# sch.net
KiCad netlist of a schematic drawn in Altium Designer
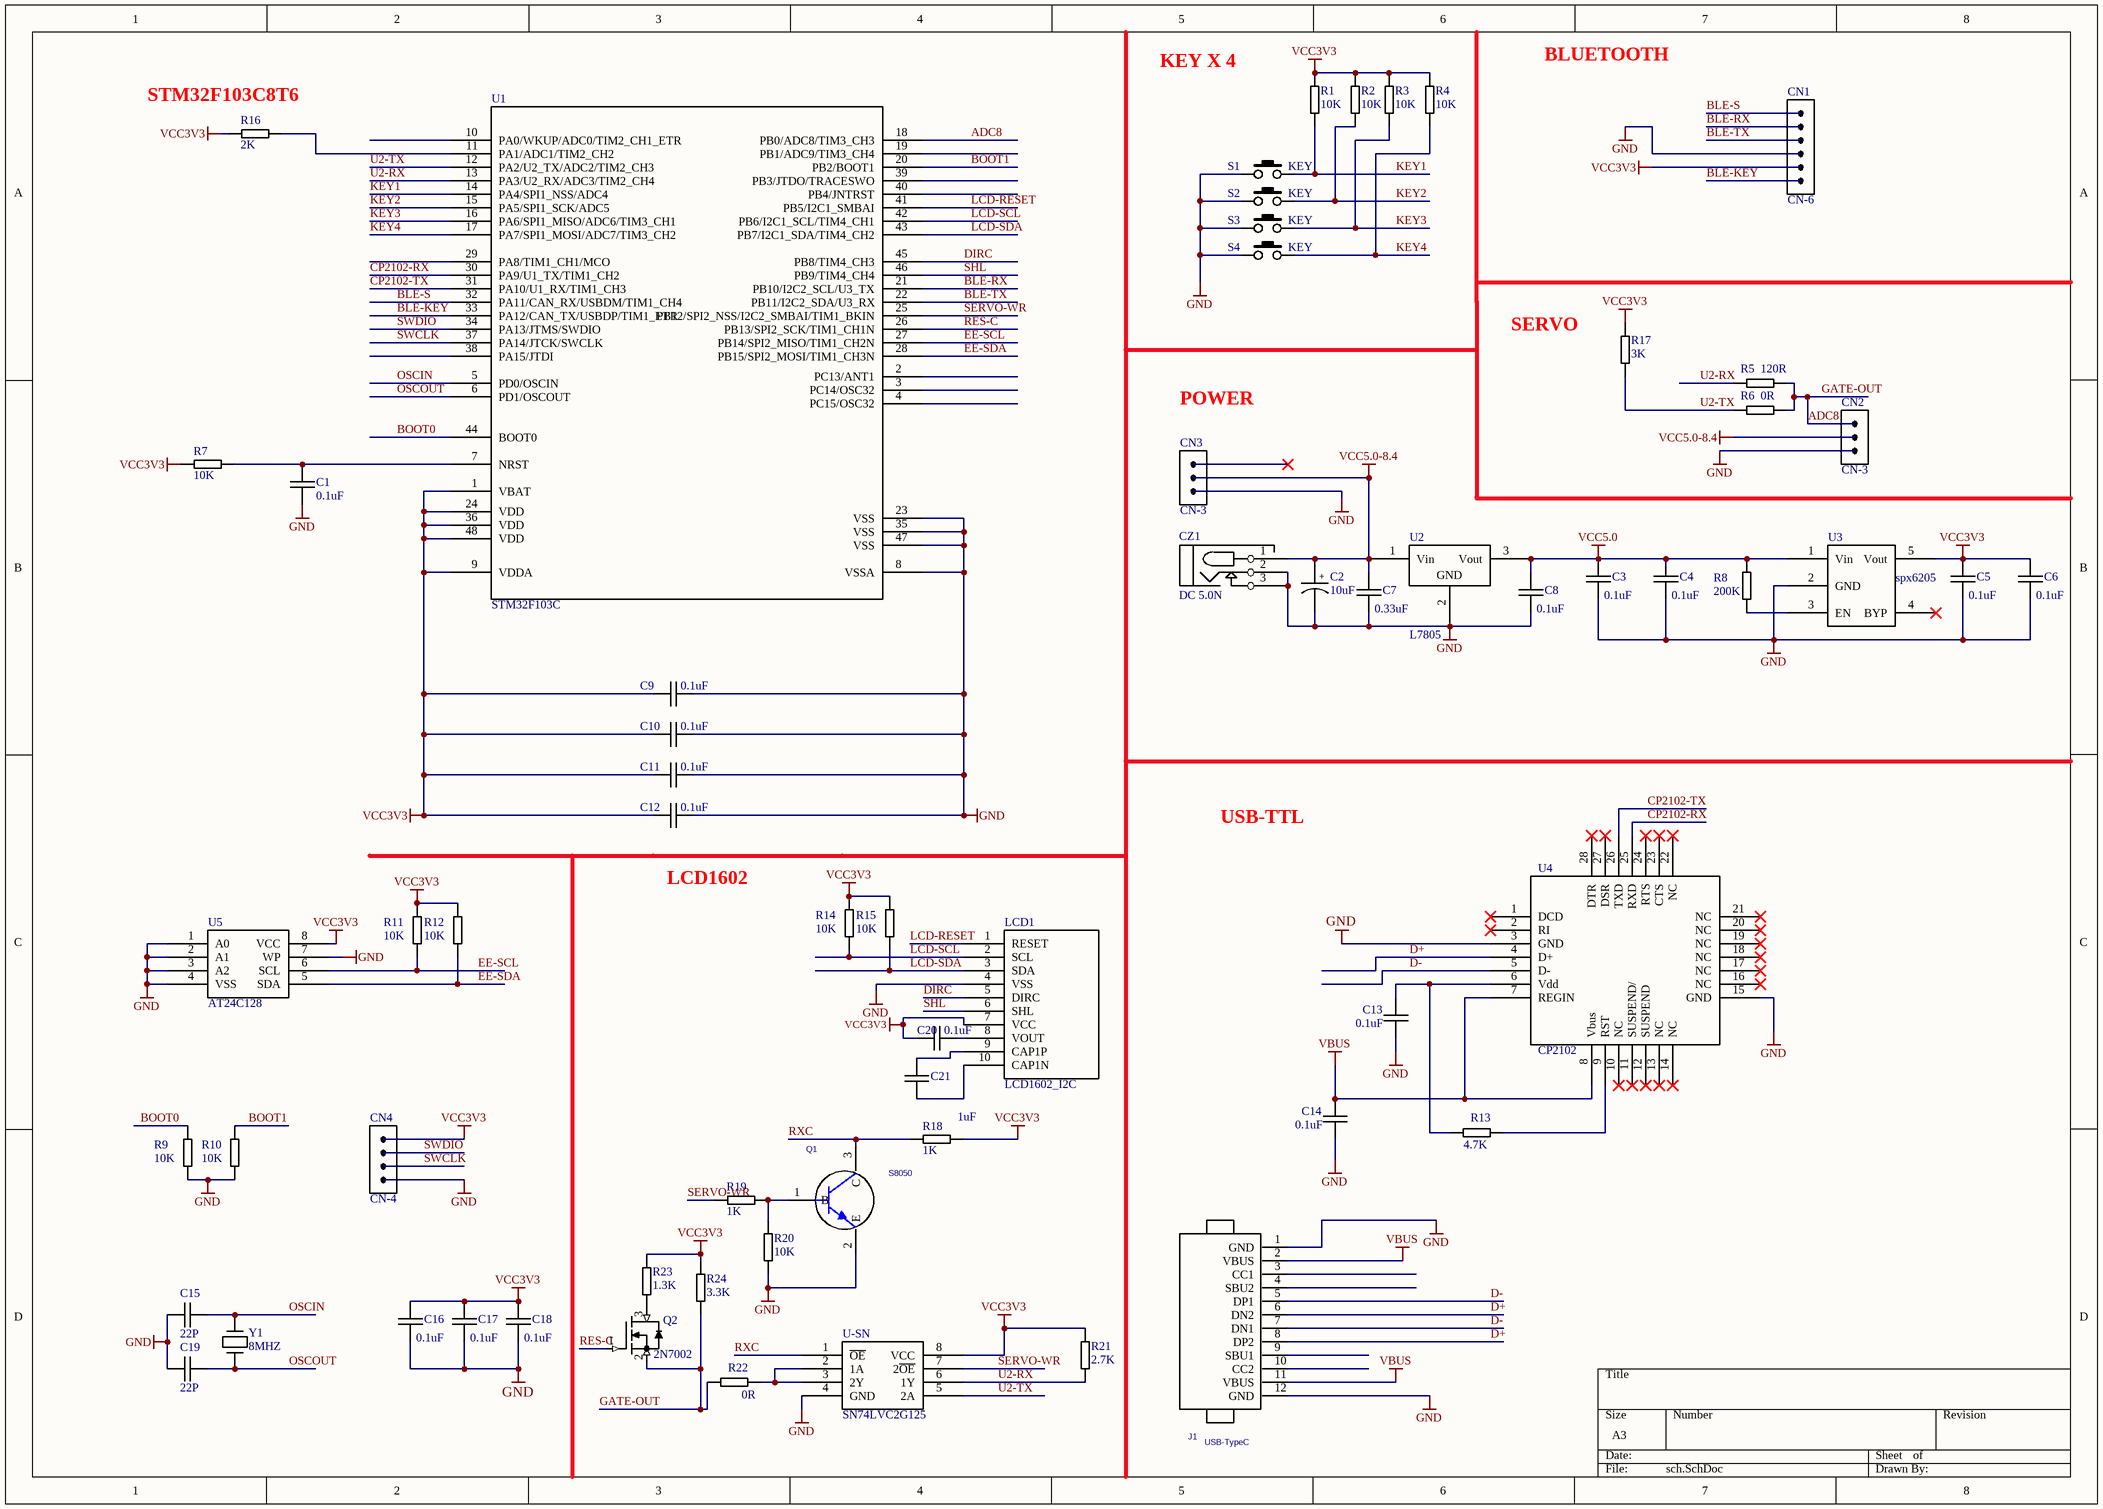
[diagram p0: sch.SchDoc]

(export (version "E")
  (design (tool "Eeschema 10.0.6"))
  (components
    (comp (ref "C1")
      (value "0.1uF")
      (footprint "CAP-0603")
      (description "Capacitor")
      (libsource (lib "综合元件") (part "CAP"))
    )
    (comp (ref "C2")
      (value "10uF")
      (footprint "CAP-A")
      (description "Polar Capacitor")
      (libsource (lib "1-Components") (part "CAP(POL)"))
    )
    (comp (ref "C3")
      (value "0.1uF")
      (footprint "CAP-0603")
      (description "Capacitor")
      (libsource (lib "综合元件") (part "CAP"))
    )
    (comp (ref "C4")
      (value "0.1uF")
      (footprint "CAP-0603")
      (description "Capacitor")
      (libsource (lib "综合元件") (part "CAP"))
    )
    (comp (ref "C5")
      (value "0.1uF")
      (footprint "CAP-0603")
      (description "Capacitor")
      (libsource (lib "综合元件") (part "CAP"))
    )
    (comp (ref "C6")
      (value "0.1uF")
      (footprint "CAP-0603")
      (description "Capacitor")
      (libsource (lib "综合元件") (part "CAP"))
    )
    (comp (ref "C7")
      (value "0.33uF")
      (footprint "CAP-0603")
      (description "Capacitor")
      (libsource (lib "综合元件") (part "CAP"))
    )
    (comp (ref "C8")
      (value "0.1uF")
      (footprint "CAP-0603")
      (description "Capacitor")
      (libsource (lib "综合元件") (part "CAP"))
    )
    (comp (ref "C9")
      (value "0.1uF")
      (footprint "CAP-0603")
      (description "Capacitor")
      (libsource (lib "综合元件") (part "CAP"))
    )
    (comp (ref "C10")
      (value "0.1uF")
      (footprint "CAP-0603")
      (description "Capacitor")
      (libsource (lib "综合元件") (part "CAP"))
    )
    (comp (ref "C11")
      (value "0.1uF")
      (footprint "CAP-0603")
      (description "Capacitor")
      (libsource (lib "综合元件") (part "CAP"))
    )
    (comp (ref "C12")
      (value "0.1uF")
      (footprint "CAP-0603")
      (description "Capacitor")
      (libsource (lib "综合元件") (part "CAP"))
    )
    (comp (ref "C13")
      (value "0.1uF")
      (footprint "CAP-0603")
      (description "Capacitor")
      (libsource (lib "综合元件") (part "CAP"))
    )
    (comp (ref "C14")
      (value "0.1uF")
      (footprint "CAP-0603")
      (description "Capacitor")
      (libsource (lib "综合元件") (part "CAP"))
    )
    (comp (ref "C15")
      (value "22P")
      (footprint "CAP-0603")
      (description "Capacitor")
      (libsource (lib "1-Components") (part "CAP"))
    )
    (comp (ref "C16")
      (value "0.1uF")
      (footprint "CAP-0603")
      (description "Capacitor")
      (libsource (lib "综合元件") (part "CAP"))
    )
    (comp (ref "C17")
      (value "0.1uF")
      (footprint "CAP-0603")
      (description "Capacitor")
      (libsource (lib "综合元件") (part "CAP"))
    )
    (comp (ref "C18")
      (value "0.1uF")
      (footprint "CAP-0603")
      (description "Capacitor")
      (libsource (lib "综合元件") (part "CAP"))
    )
    (comp (ref "C19")
      (value "22P")
      (footprint "CAP-0603")
      (description "Capacitor")
      (libsource (lib "1-Components") (part "CAP"))
    )
    (comp (ref "C20")
      (value "0.1uF")
      (footprint "CAP-0603")
      (description "Capacitor")
      (libsource (lib "综合元件") (part "CAP"))
    )
    (comp (ref "C21")
      (value "1uF")
      (footprint "CAP-0603")
      (description "Capacitor")
      (libsource (lib "综合元件") (part "CAP"))
    )
    (comp (ref "CN1") (value "CN-6") (footprint "CN-6") (libsource (lib "2-Connectors") (part "CN-6")))
    (comp (ref "CN2") (value "CN-3") (footprint "IDC-3×1") (libsource (lib "2-Connectors") (part "CN-3")))
    (comp (ref "CN3") (value "CN-3") (footprint "IDC-3×1") (libsource (lib "2-Connectors") (part "CN-3")))
    (comp (ref "CN4") (value "CN-4") (footprint "IDC-4×1") (libsource (lib "2-Connectors") (part "CN-4")))
    (comp (ref "CZ1")
      (value "DC 5.0N")
      (footprint "DC-005(N)")
      (libsource (lib "2-Connectors") (part "DC 5.0N"))
    )
    (comp (ref "J1")
      (value "USB-TypeC")
      (footprint "USB-TYPEC")
      (libsource (lib "2-Connectors") (part "USB-TypeC"))
    )
    (comp (ref "LCD1")
      (value "LCD1602_I2C")
      (footprint "LCD-IIC")
      (description "LCD1602")
      (libsource (lib "6-Modulars") (part "LCD1602_I2C"))
    )
    (comp (ref "Q1")
      (value "S8050")
      (footprint "SOT-23(3)")
      (description "NPN")
      (libsource (lib "3-ICs Normal") (part "S8050"))
    )
    (comp (ref "Q2")
      (value "2N7002")
      (footprint "SOT-23(3)")
      (libsource (lib "1-Components") (part "FET(N)_SOT"))
    )
    (comp (ref "R1")
      (value "10K")
      (footprint "RES-0603")
      (description "Resistor")
      (libsource (lib "1-Components") (part "RES"))
    )
    (comp (ref "R2")
      (value "10K")
      (footprint "RES-0603")
      (description "Resistor")
      (libsource (lib "1-Components") (part "RES"))
    )
    (comp (ref "R3")
      (value "10K")
      (footprint "RES-0603")
      (description "Resistor")
      (libsource (lib "1-Components") (part "RES"))
    )
    (comp (ref "R4")
      (value "10K")
      (footprint "RES-0603")
      (description "Resistor")
      (libsource (lib "1-Components") (part "RES"))
    )
    (comp (ref "R5")
      (value "120R")
      (footprint "RES-0603")
      (description "Resistor")
      (libsource (lib "1-Components") (part "RES"))
    )
    (comp (ref "R6")
      (value "0R")
      (footprint "RES-0603")
      (description "Resistor")
      (libsource (lib "1-Components") (part "RES"))
    )
    (comp (ref "R7")
      (value "10K")
      (footprint "RES-0603")
      (description "Resistor")
      (libsource (lib "综合元件") (part "RES"))
    )
    (comp (ref "R8")
      (value "200K")
      (footprint "RES-0603")
      (description "Resistor")
      (libsource (lib "1-Components") (part "RES"))
    )
    (comp (ref "R9")
      (value "10K")
      (footprint "RES-0603")
      (description "Resistor")
      (libsource (lib "1-Components") (part "RES"))
    )
    (comp (ref "R10")
      (value "10K")
      (footprint "RES-0603")
      (description "Resistor")
      (libsource (lib "1-Components") (part "RES"))
    )
    (comp (ref "R11")
      (value "10K")
      (footprint "RES-0603")
      (description "Resistor")
      (libsource (lib "1-Components") (part "RES"))
    )
    (comp (ref "R12")
      (value "10K")
      (footprint "RES-0603")
      (description "Resistor")
      (libsource (lib "1-Components") (part "RES"))
    )
    (comp (ref "R13")
      (value "4.7K")
      (footprint "RES-0603")
      (description "Resistor")
      (libsource (lib "1-Components") (part "RES"))
    )
    (comp (ref "R14")
      (value "10K")
      (footprint "RES-0603")
      (description "Resistor")
      (libsource (lib "1-Components") (part "RES"))
    )
    (comp (ref "R15")
      (value "10K")
      (footprint "RES-0603")
      (description "Resistor")
      (libsource (lib "1-Components") (part "RES"))
    )
    (comp (ref "R16")
      (value "2K")
      (footprint "RES-0603")
      (description "Resistor")
      (libsource (lib "1-Components") (part "RES"))
    )
    (comp (ref "R17")
      (value "3K")
      (footprint "RES-0603")
      (description "Resistor")
      (libsource (lib "1-Components") (part "RES"))
    )
    (comp (ref "R18")
      (value "1K")
      (footprint "RES-0603")
      (description "Resistor")
      (libsource (lib "1-Components") (part "RES"))
    )
    (comp (ref "R19")
      (value "1K")
      (footprint "RES-0603")
      (description "Resistor")
      (libsource (lib "1-Components") (part "RES"))
    )
    (comp (ref "R20")
      (value "10K")
      (footprint "RES-0603")
      (description "Resistor")
      (libsource (lib "1-Components") (part "RES"))
    )
    (comp (ref "R21")
      (value "2.7K")
      (footprint "RES-0603")
      (description "Resistor")
      (libsource (lib "1-Components") (part "RES"))
    )
    (comp (ref "R22")
      (value "0R")
      (footprint "RES-0603")
      (description "Resistor")
      (libsource (lib "1-Components") (part "RES"))
    )
    (comp (ref "R23")
      (value "1.3K")
      (footprint "RES-0603")
      (description "Resistor")
      (libsource (lib "1-Components") (part "RES"))
    )
    (comp (ref "R24")
      (value "3.3K")
      (footprint "RES-0603")
      (description "Resistor")
      (libsource (lib "1-Components") (part "RES"))
    )
    (comp (ref "S1") (value "KEY") (footprint "KEY-4X4X1.5") (libsource (lib "2-Connectors") (part "KEY")))
    (comp (ref "S2") (value "KEY") (footprint "KEY-4X4X1.5") (libsource (lib "2-Connectors") (part "KEY")))
    (comp (ref "S3") (value "KEY") (footprint "KEY-4X4X1.5") (libsource (lib "2-Connectors") (part "KEY")))
    (comp (ref "S4") (value "KEY") (footprint "KEY-4X4X1.5") (libsource (lib "2-Connectors") (part "KEY")))
    (comp (ref "U-SN")
      (value "SN74LVC2G125")
      (footprint "SOP-8(SN74)")
      (libsource (lib "3-ICs Normal") (part "SN74LVC2G125"))
    )
    (comp (ref "U1")
      (value "STM32F103C")
      (footprint "LQFP-48")
      (fields (field (name "PUBLISHER") "Altium Limited"))
      (libsource (lib "5-ICs Mcu") (part "STM32F103C(LQFP)"))
    )
    (comp (ref "U2") (value "L7805") (footprint "TO-252") (libsource (lib "3-ICs Normal") (part "78XX")))
    (comp (ref "U3")
      (value "spx6205")
      (footprint "SOT-23(5)")
      (libsource (lib "3-ICs Normal") (part "SP6205(FIXED)"))
    )
    (comp (ref "U4") (value "CP2102") (footprint "QFN-28") (libsource (lib "5-ICs Mcu") (part "MPU6050_1")))
    (comp (ref "U5")
      (value "AT24C128")
      (footprint "SOP-8(3.9)")
      (libsource (lib "3-ICs Normal") (part "AT24C128"))
    )
    (comp (ref "Y1")
      (value "8MHZ")
      (footprint "XTAL-2512")
      (description "Crystal")
      (libsource (lib "1-Components") (part "XTAL(1)"))
    )
  )
  (nets
    (net (code "1") (name "/ADC8") (class "Default")
      (node (ref "CN2") (pin "1") (pinfunction "1_1") (pintype "passive"))
      (node (ref "Q2") (pin "2") (pinfunction "S_2") (pintype "input"))
      (node (ref "R22") (pin "2") (pinfunction "2_2") (pintype "passive"))
      (node (ref "R24") (pin "1") (pinfunction "1_1") (pintype "passive"))
      (node (ref "R5") (pin "2") (pinfunction "2_2") (pintype "passive"))
      (node (ref "R6") (pin "2") (pinfunction "2_2") (pintype "passive"))
      (node (ref "U1") (pin "18") (pinfunction "PB0/ADC8/TIM3_CH3_18") (pintype "passive"))
    )
    (net (code "2") (name "/BLE-KEY") (class "Default")
      (node (ref "CN1") (pin "6") (pinfunction "6_6") (pintype "passive"))
      (node (ref "U1") (pin "33") (pinfunction "PA12/CAN_TX/USBDP/TIM1_ETR_33") (pintype "passive"))
    )
    (net (code "3") (name "/BLE-RX") (class "Default")
      (node (ref "CN1") (pin "2") (pinfunction "2_2") (pintype "passive"))
      (node (ref "U1") (pin "21") (pinfunction "PB10/I2C2_SCL/U3_TX_21") (pintype "passive"))
    )
    (net (code "4") (name "/BLE-S") (class "Default")
      (node (ref "CN1") (pin "1") (pinfunction "1_1") (pintype "passive"))
      (node (ref "U1") (pin "32") (pinfunction "PA11/CAN_RX/USBDM/TIM1_CH4_32") (pintype "passive"))
    )
    (net (code "5") (name "/BLE-TX") (class "Default")
      (node (ref "CN1") (pin "3") (pinfunction "3_3") (pintype "passive"))
      (node (ref "U1") (pin "22") (pinfunction "PB11/I2C2_SDA/U3_RX_22") (pintype "passive"))
    )
    (net (code "6") (name "/BOOT0") (class "Default")
      (node (ref "R9") (pin "1") (pinfunction "1_1") (pintype "passive"))
      (node (ref "U1") (pin "44") (pinfunction "BOOT0_44") (pintype "passive"))
    )
    (net (code "7") (name "/BOOT1") (class "Default")
      (node (ref "R10") (pin "1") (pinfunction "1_1") (pintype "passive"))
      (node (ref "U1") (pin "20") (pinfunction "PB2/BOOT1_20") (pintype "passive"))
    )
    (net (code "8") (name "/CP2102-RX") (class "Default")
      (node (ref "U1") (pin "30") (pinfunction "PA9/U1_TX/TIM1_CH2_30") (pintype "passive"))
      (node (ref "U4") (pin "25") (pinfunction "RXD_25") (pintype "passive"))
    )
    (net (code "9") (name "/CP2102-TX") (class "Default")
      (node (ref "U1") (pin "31") (pinfunction "PA10/U1_RX/TIM1_CH3_31") (pintype "passive"))
      (node (ref "U4") (pin "26") (pinfunction "TXD_26") (pintype "passive"))
    )
    (net (code "10") (name "/D+") (class "Default")
      (node (ref "J1") (pin "6") (pinfunction "DN2_6") (pintype "passive"))
      (node (ref "J1") (pin "8") (pinfunction "DP2_8") (pintype "passive"))
      (node (ref "U4") (pin "4") (pinfunction "D+_4") (pintype "passive"))
    )
    (net (code "11") (name "/D-") (class "Default")
      (node (ref "J1") (pin "5") (pinfunction "DP1_5") (pintype "passive"))
      (node (ref "J1") (pin "7") (pinfunction "DN1_7") (pintype "passive"))
      (node (ref "U4") (pin "5") (pinfunction "D-_5") (pintype "passive"))
    )
    (net (code "12") (name "/DIRC") (class "Default")
      (node (ref "LCD1") (pin "5") (pinfunction "DIRC_5") (pintype "passive"))
      (node (ref "U1") (pin "45") (pinfunction "PB8/TIM4_CH3_45") (pintype "passive"))
    )
    (net (code "13") (name "/EE-SCL") (class "Default")
      (node (ref "R11") (pin "2") (pinfunction "2_2") (pintype "passive"))
      (node (ref "U1") (pin "27") (pinfunction "PB14/SPI2_MISO/TIM1_CH2N_27") (pintype "passive"))
      (node (ref "U5") (pin "6") (pinfunction "SCL_6") (pintype "passive"))
    )
    (net (code "14") (name "/EE-SDA") (class "Default")
      (node (ref "R12") (pin "2") (pinfunction "2_2") (pintype "passive"))
      (node (ref "U1") (pin "28") (pinfunction "PB15/SPI2_MOSI/TIM1_CH3N_28") (pintype "passive"))
      (node (ref "U5") (pin "5") (pinfunction "SDA_5") (pintype "passive"))
    )
    (net (code "15") (name "/KEY1") (class "Default")
      (node (ref "R1") (pin "1") (pinfunction "1_1") (pintype "passive"))
      (node (ref "S1") (pin "2") (pinfunction "2_2") (pintype "passive"))
      (node (ref "U1") (pin "14") (pinfunction "PA4/SPI1_NSS/ADC4_14") (pintype "passive"))
    )
    (net (code "16") (name "/KEY2") (class "Default")
      (node (ref "R2") (pin "1") (pinfunction "1_1") (pintype "passive"))
      (node (ref "S2") (pin "2") (pinfunction "2_2") (pintype "passive"))
      (node (ref "U1") (pin "15") (pinfunction "PA5/SPI1_SCK/ADC5_15") (pintype "passive"))
    )
    (net (code "17") (name "/KEY3") (class "Default")
      (node (ref "R3") (pin "1") (pinfunction "1_1") (pintype "passive"))
      (node (ref "S3") (pin "2") (pinfunction "2_2") (pintype "passive"))
      (node (ref "U1") (pin "16") (pinfunction "PA6/SPI1_MISO/ADC6/TIM3_CH1_16") (pintype "passive"))
    )
    (net (code "18") (name "/KEY4") (class "Default")
      (node (ref "R4") (pin "1") (pinfunction "1_1") (pintype "passive"))
      (node (ref "S4") (pin "2") (pinfunction "2_2") (pintype "passive"))
      (node (ref "U1") (pin "17") (pinfunction "PA7/SPI1_MOSI/ADC7/TIM3_CH2_17") (pintype "passive"))
    )
    (net (code "19") (name "/LCD-RESET") (class "Default")
      (node (ref "LCD1") (pin "1") (pinfunction "RESET_1") (pintype "passive"))
      (node (ref "U1") (pin "41") (pinfunction "PB5/I2C1_SMBAI_41") (pintype "passive"))
    )
    (net (code "20") (name "/LCD-SCL") (class "Default")
      (node (ref "LCD1") (pin "2") (pinfunction "SCL_2") (pintype "passive"))
      (node (ref "R14") (pin "2") (pinfunction "2_2") (pintype "passive"))
      (node (ref "U1") (pin "42") (pinfunction "PB6/I2C1_SCL/TIM4_CH1_42") (pintype "passive"))
    )
    (net (code "21") (name "/LCD-SDA") (class "Default")
      (node (ref "LCD1") (pin "3") (pinfunction "SDA_3") (pintype "passive"))
      (node (ref "R15") (pin "2") (pinfunction "2_2") (pintype "passive"))
      (node (ref "U1") (pin "43") (pinfunction "PB7/I2C1_SDA/TIM4_CH2_43") (pintype "passive"))
    )
    (net (code "22") (name "/OSCIN") (class "Default")
      (node (ref "C15") (pin "2") (pinfunction "2_2") (pintype "passive"))
      (node (ref "U1") (pin "5") (pinfunction "PD0/OSCIN_5") (pintype "passive"))
      (node (ref "Y1") (pin "2") (pinfunction "2_2") (pintype "passive"))
    )
    (net (code "23") (name "/OSCOUT") (class "Default")
      (node (ref "C19") (pin "2") (pinfunction "2_2") (pintype "passive"))
      (node (ref "U1") (pin "6") (pinfunction "PD1/OSCOUT_6") (pintype "passive"))
      (node (ref "Y1") (pin "1") (pinfunction "1_1") (pintype "passive"))
    )
    (net (code "24") (name "/RES-C") (class "Default")
      (node (ref "Q2") (pin "1") (pinfunction "G_1") (pintype "input"))
      (node (ref "U1") (pin "26") (pinfunction "PB13/SPI2_SCK/TIM1_CH1N_26") (pintype "passive"))
    )
    (net (code "25") (name "/RXC") (class "Default")
      (node (ref "Q1") (pin "3") (pinfunction "C_3") (pintype "passive"))
      (node (ref "R18") (pin "1") (pinfunction "1_1") (pintype "passive"))
      (node (ref "U-SN") (pin "1") (pinfunction "~{OE}_1") (pintype "passive"))
    )
    (net (code "26") (name "/SERVO-WR") (class "Default")
      (node (ref "R19") (pin "1") (pinfunction "1_1") (pintype "passive"))
      (node (ref "U-SN") (pin "7") (pinfunction "2~{OE}_7") (pintype "passive"))
      (node (ref "U1") (pin "25") (pinfunction "PB12/SPI2_NSS/I2C2_SMBAI/TIM1_BKIN_25") (pintype "passive"))
    )
    (net (code "27") (name "/SHL") (class "Default")
      (node (ref "LCD1") (pin "6") (pinfunction "SHL_6") (pintype "passive"))
      (node (ref "U1") (pin "46") (pinfunction "PB9/TIM4_CH4_46") (pintype "passive"))
    )
    (net (code "28") (name "/SWCLK") (class "Default")
      (node (ref "CN4") (pin "3") (pinfunction "3_3") (pintype "passive"))
      (node (ref "U1") (pin "37") (pinfunction "PA14/JTCK/SWCLK_37") (pintype "passive"))
    )
    (net (code "29") (name "/SWDIO") (class "Default")
      (node (ref "CN4") (pin "2") (pinfunction "2_2") (pintype "passive"))
      (node (ref "U1") (pin "34") (pinfunction "PA13/JTMS/SWDIO_34") (pintype "passive"))
    )
    (net (code "30") (name "/U2-RX") (class "Default")
      (node (ref "R21") (pin "1") (pinfunction "1_1") (pintype "passive"))
      (node (ref "R5") (pin "1") (pinfunction "1_1") (pintype "passive"))
      (node (ref "U-SN") (pin "6") (pinfunction "1Y_6") (pintype "passive"))
      (node (ref "U1") (pin "13") (pinfunction "PA3/U2_RX/ADC3/TIM2_CH4_13") (pintype "passive"))
    )
    (net (code "31") (name "/U2-TX") (class "Default")
      (node (ref "R17") (pin "1") (pinfunction "1_1") (pintype "passive"))
      (node (ref "R6") (pin "1") (pinfunction "1_1") (pintype "passive"))
      (node (ref "U-SN") (pin "5") (pinfunction "2A_5") (pintype "passive"))
      (node (ref "U1") (pin "12") (pinfunction "PA2/U2_TX/ADC2/TIM2_CH3_12") (pintype "passive"))
    )
    (net (code "32") (name "GND") (class "Default")
      (node (ref "C1") (pin "2") (pinfunction "2_2") (pintype "passive"))
      (node (ref "C10") (pin "1") (pinfunction "1_1") (pintype "passive"))
      (node (ref "C11") (pin "1") (pinfunction "1_1") (pintype "passive"))
      (node (ref "C12") (pin "1") (pinfunction "1_1") (pintype "passive"))
      (node (ref "C13") (pin "2") (pinfunction "2_2") (pintype "passive"))
      (node (ref "C14") (pin "2") (pinfunction "2_2") (pintype "passive"))
      (node (ref "C15") (pin "1") (pinfunction "1_1") (pintype "passive"))
      (node (ref "C16") (pin "2") (pinfunction "2_2") (pintype "passive"))
      (node (ref "C17") (pin "2") (pinfunction "2_2") (pintype "passive"))
      (node (ref "C18") (pin "2") (pinfunction "2_2") (pintype "passive"))
      (node (ref "C19") (pin "1") (pinfunction "1_1") (pintype "passive"))
      (node (ref "C2") (pin "2") (pinfunction "2_2") (pintype "passive"))
      (node (ref "C3") (pin "2") (pinfunction "2_2") (pintype "passive"))
      (node (ref "C4") (pin "2") (pinfunction "2_2") (pintype "passive"))
      (node (ref "C5") (pin "2") (pinfunction "2_2") (pintype "passive"))
      (node (ref "C6") (pin "2") (pinfunction "2_2") (pintype "passive"))
      (node (ref "C7") (pin "2") (pinfunction "2_2") (pintype "passive"))
      (node (ref "C8") (pin "2") (pinfunction "2_2") (pintype "passive"))
      (node (ref "C9") (pin "1") (pinfunction "1_1") (pintype "passive"))
      (node (ref "CN1") (pin "4") (pinfunction "4_4") (pintype "passive"))
      (node (ref "CN2") (pin "3") (pinfunction "3_3") (pintype "passive"))
      (node (ref "CN3") (pin "3") (pinfunction "3_3") (pintype "passive"))
      (node (ref "CN4") (pin "4") (pinfunction "4_4") (pintype "passive"))
      (node (ref "CZ1") (pin "2") (pinfunction "A_2") (pintype "passive"))
      (node (ref "CZ1") (pin "3") (pinfunction "B_3") (pintype "passive"))
      (node (ref "J1") (pin "1") (pinfunction "GND_1") (pintype "passive"))
      (node (ref "J1") (pin "12") (pinfunction "GND_12") (pintype "passive"))
      (node (ref "LCD1") (pin "4") (pinfunction "VSS_4") (pintype "passive"))
      (node (ref "Q1") (pin "2") (pinfunction "E_2") (pintype "passive"))
      (node (ref "R10") (pin "2") (pinfunction "2_2") (pintype "passive"))
      (node (ref "R20") (pin "2") (pinfunction "2_2") (pintype "passive"))
      (node (ref "R9") (pin "2") (pinfunction "2_2") (pintype "passive"))
      (node (ref "S1") (pin "1") (pinfunction "1_1") (pintype "passive"))
      (node (ref "S2") (pin "1") (pinfunction "1_1") (pintype "passive"))
      (node (ref "S3") (pin "1") (pinfunction "1_1") (pintype "passive"))
      (node (ref "S4") (pin "1") (pinfunction "1_1") (pintype "passive"))
      (node (ref "U-SN") (pin "4") (pinfunction "GND_4") (pintype "passive"))
      (node (ref "U1") (pin "23") (pinfunction "VSS_23") (pintype "passive"))
      (node (ref "U1") (pin "35") (pinfunction "VSS_35") (pintype "passive"))
      (node (ref "U1") (pin "47") (pinfunction "VSS_47") (pintype "passive"))
      (node (ref "U1") (pin "8") (pinfunction "VSSA_8") (pintype "passive"))
      (node (ref "U2") (pin "2") (pinfunction "GND_2") (pintype "passive"))
      (node (ref "U3") (pin "2") (pinfunction "GND_2") (pintype "passive"))
      (node (ref "U4") (pin "15") (pinfunction "GND_15") (pintype "passive"))
      (node (ref "U4") (pin "3") (pinfunction "GND_3") (pintype "passive"))
      (node (ref "U5") (pin "1") (pinfunction "A0_1") (pintype "passive"))
      (node (ref "U5") (pin "2") (pinfunction "A1_2") (pintype "passive"))
      (node (ref "U5") (pin "3") (pinfunction "A2_3") (pintype "passive"))
      (node (ref "U5") (pin "4") (pinfunction "VSS_4") (pintype "passive"))
      (node (ref "U5") (pin "7") (pinfunction "WP_7") (pintype "passive"))
    )
    (net (code "33") (name "Net-(LCD1-CAP1N)") (class "Default")
      (node (ref "C21") (pin "2") (pinfunction "2_2") (pintype "passive"))
      (node (ref "LCD1") (pin "10") (pinfunction "CAP1N_10") (pintype "passive"))
    )
    (net (code "34") (name "Net-(LCD1-CAP1P)") (class "Default")
      (node (ref "C21") (pin "1") (pinfunction "1_1") (pintype "passive"))
      (node (ref "LCD1") (pin "9") (pinfunction "CAP1P_9") (pintype "passive"))
    )
    (net (code "35") (name "Net-(LCD1-VOUT)") (class "Default")
      (node (ref "C20") (pin "2") (pinfunction "2_2") (pintype "passive"))
      (node (ref "LCD1") (pin "8") (pinfunction "VOUT_8") (pintype "passive"))
    )
    (net (code "36") (name "Net-(Q1-B)") (class "Default")
      (node (ref "Q1") (pin "1") (pinfunction "B_1") (pintype "passive"))
      (node (ref "R19") (pin "2") (pinfunction "2_2") (pintype "passive"))
      (node (ref "R20") (pin "1") (pinfunction "1_1") (pintype "passive"))
    )
    (net (code "37") (name "Net-(Q2-D)") (class "Default")
      (node (ref "Q2") (pin "3") (pinfunction "D_3") (pintype "input"))
      (node (ref "R23") (pin "1") (pinfunction "1_1") (pintype "passive"))
    )
    (net (code "38") (name "Net-(U-SN-1A)") (class "Default")
      (node (ref "R22") (pin "1") (pinfunction "1_1") (pintype "passive"))
      (node (ref "U-SN") (pin "2") (pinfunction "1A_2") (pintype "passive"))
      (node (ref "U-SN") (pin "3") (pinfunction "2Y_3") (pintype "passive"))
    )
    (net (code "39") (name "Net-(U1-NRST)") (class "Default")
      (node (ref "C1") (pin "1") (pinfunction "1_1") (pintype "passive"))
      (node (ref "R7") (pin "2") (pinfunction "2_2") (pintype "passive"))
      (node (ref "U1") (pin "7") (pinfunction "NRST_7") (pintype "passive"))
    )
    (net (code "40") (name "Net-(U1-PA1{slash}ADC1{slash}TIM2_CH2)") (class "Default")
      (node (ref "R16") (pin "1") (pinfunction "1_1") (pintype "passive"))
      (node (ref "U1") (pin "11") (pinfunction "PA1/ADC1/TIM2_CH2_11") (pintype "passive"))
    )
    (net (code "41") (name "Net-(U3-EN)") (class "Default")
      (node (ref "R8") (pin "2") (pinfunction "2_2") (pintype "passive"))
      (node (ref "U3") (pin "3") (pinfunction "EN_3") (pintype "passive"))
    )
    (net (code "42") (name "Net-(U4-RST)") (class "Default")
      (node (ref "R13") (pin "2") (pinfunction "2_2") (pintype "passive"))
      (node (ref "U4") (pin "9") (pinfunction "RST_9") (pintype "passive"))
    )
    (net (code "43") (name "Net-(U4-Vdd)") (class "Default")
      (node (ref "C13") (pin "1") (pinfunction "1_1") (pintype "passive"))
      (node (ref "R13") (pin "1") (pinfunction "1_1") (pintype "passive"))
      (node (ref "U4") (pin "6") (pinfunction "Vdd_6") (pintype "passive"))
    )
    (net (code "44") (name "VBUS") (class "Default")
      (node (ref "C14") (pin "1") (pinfunction "1_1") (pintype "passive"))
      (node (ref "J1") (pin "11") (pinfunction "VBUS_11") (pintype "passive"))
      (node (ref "J1") (pin "2") (pinfunction "VBUS_2") (pintype "passive"))
      (node (ref "U4") (pin "7") (pinfunction "REGIN_7") (pintype "passive"))
      (node (ref "U4") (pin "8") (pinfunction "Vbus_8") (pintype "passive"))
    )
    (net (code "45") (name "VCC3V3") (class "Default")
      (node (ref "C10") (pin "2") (pinfunction "2_2") (pintype "passive"))
      (node (ref "C11") (pin "2") (pinfunction "2_2") (pintype "passive"))
      (node (ref "C12") (pin "2") (pinfunction "2_2") (pintype "passive"))
      (node (ref "C16") (pin "1") (pinfunction "1_1") (pintype "passive"))
      (node (ref "C17") (pin "1") (pinfunction "1_1") (pintype "passive"))
      (node (ref "C18") (pin "1") (pinfunction "1_1") (pintype "passive"))
      (node (ref "C20") (pin "1") (pinfunction "1_1") (pintype "passive"))
      (node (ref "C5") (pin "1") (pinfunction "1_1") (pintype "passive"))
      (node (ref "C6") (pin "1") (pinfunction "1_1") (pintype "passive"))
      (node (ref "C9") (pin "2") (pinfunction "2_2") (pintype "passive"))
      (node (ref "CN1") (pin "5") (pinfunction "5_5") (pintype "passive"))
      (node (ref "CN4") (pin "1") (pinfunction "1_1") (pintype "passive"))
      (node (ref "LCD1") (pin "7") (pinfunction "VCC_7") (pintype "passive"))
      (node (ref "R1") (pin "2") (pinfunction "2_2") (pintype "passive"))
      (node (ref "R11") (pin "1") (pinfunction "1_1") (pintype "passive"))
      (node (ref "R12") (pin "1") (pinfunction "1_1") (pintype "passive"))
      (node (ref "R14") (pin "1") (pinfunction "1_1") (pintype "passive"))
      (node (ref "R15") (pin "1") (pinfunction "1_1") (pintype "passive"))
      (node (ref "R16") (pin "2") (pinfunction "2_2") (pintype "passive"))
      (node (ref "R17") (pin "2") (pinfunction "2_2") (pintype "passive"))
      (node (ref "R18") (pin "2") (pinfunction "2_2") (pintype "passive"))
      (node (ref "R2") (pin "2") (pinfunction "2_2") (pintype "passive"))
      (node (ref "R21") (pin "2") (pinfunction "2_2") (pintype "passive"))
      (node (ref "R23") (pin "2") (pinfunction "2_2") (pintype "passive"))
      (node (ref "R24") (pin "2") (pinfunction "2_2") (pintype "passive"))
      (node (ref "R3") (pin "2") (pinfunction "2_2") (pintype "passive"))
      (node (ref "R4") (pin "2") (pinfunction "2_2") (pintype "passive"))
      (node (ref "R7") (pin "1") (pinfunction "1_1") (pintype "passive"))
      (node (ref "U-SN") (pin "8") (pinfunction "VCC_8") (pintype "passive"))
      (node (ref "U1") (pin "1") (pinfunction "VBAT_1") (pintype "passive"))
      (node (ref "U1") (pin "24") (pinfunction "VDD_24") (pintype "passive"))
      (node (ref "U1") (pin "36") (pinfunction "VDD_36") (pintype "passive"))
      (node (ref "U1") (pin "48") (pinfunction "VDD_48") (pintype "passive"))
      (node (ref "U1") (pin "9") (pinfunction "VDDA_9") (pintype "passive"))
      (node (ref "U3") (pin "5") (pinfunction "Vout_5") (pintype "passive"))
      (node (ref "U5") (pin "8") (pinfunction "VCC_8") (pintype "passive"))
    )
    (net (code "46") (name "VCC5.0") (class "Default")
      (node (ref "C3") (pin "1") (pinfunction "1_1") (pintype "passive"))
      (node (ref "C4") (pin "1") (pinfunction "1_1") (pintype "passive"))
      (node (ref "C8") (pin "1") (pinfunction "1_1") (pintype "passive"))
      (node (ref "R8") (pin "1") (pinfunction "1_1") (pintype "passive"))
      (node (ref "U2") (pin "3") (pinfunction "Vout_3") (pintype "passive"))
      (node (ref "U3") (pin "1") (pinfunction "Vin_1") (pintype "passive"))
    )
    (net (code "47") (name "VCC5.0-8.4") (class "Default")
      (node (ref "C2") (pin "1") (pinfunction "1_1") (pintype "passive"))
      (node (ref "C7") (pin "1") (pinfunction "1_1") (pintype "passive"))
      (node (ref "CN2") (pin "2") (pinfunction "2_2") (pintype "passive"))
      (node (ref "CN3") (pin "2") (pinfunction "2_2") (pintype "passive"))
      (node (ref "CZ1") (pin "1") (pinfunction "+_1") (pintype "passive"))
      (node (ref "U2") (pin "1") (pinfunction "Vin_1") (pintype "passive"))
    )
    (net (code "48") (name "unconnected-(CN3-Pad1)") (class "Default")
      (node (ref "CN3") (pin "1") (pinfunction "1_1") (pintype "passive+no_connect"))
    )
    (net (code "49") (name "unconnected-(J1-CC1-Pad3)") (class "Default")
      (node (ref "J1") (pin "3") (pinfunction "CC1_3") (pintype "passive"))
    )
    (net (code "50") (name "unconnected-(J1-CC2-Pad10)") (class "Default")
      (node (ref "J1") (pin "10") (pinfunction "CC2_10") (pintype "passive"))
    )
    (net (code "51") (name "unconnected-(J1-SBU1-Pad9)") (class "Default")
      (node (ref "J1") (pin "9") (pinfunction "SBU1_9") (pintype "passive"))
    )
    (net (code "52") (name "unconnected-(J1-SBU2-Pad4)") (class "Default")
      (node (ref "J1") (pin "4") (pinfunction "SBU2_4") (pintype "passive"))
    )
    (net (code "53") (name "unconnected-(U1-PA0{slash}WKUP{slash}ADC0{slash}TIM2_CH1_ETR-Pad10)") (class "Default")
      (node (ref "U1") (pin "10") (pinfunction "PA0/WKUP/ADC0/TIM2_CH1_ETR_10") (pintype "passive"))
    )
    (net (code "54") (name "unconnected-(U1-PA8{slash}TIM1_CH1{slash}MCO-Pad29)") (class "Default")
      (node (ref "U1") (pin "29") (pinfunction "PA8/TIM1_CH1/MCO_29") (pintype "passive"))
    )
    (net (code "55") (name "unconnected-(U1-PA15{slash}JTDI-Pad38)") (class "Default")
      (node (ref "U1") (pin "38") (pinfunction "PA15/JTDI_38") (pintype "passive"))
    )
    (net (code "56") (name "unconnected-(U1-PB1{slash}ADC9{slash}TIM3_CH4-Pad19)") (class "Default")
      (node (ref "U1") (pin "19") (pinfunction "PB1/ADC9/TIM3_CH4_19") (pintype "passive"))
    )
    (net (code "57") (name "unconnected-(U1-PB3{slash}JTDO{slash}TRACESWO-Pad39)") (class "Default")
      (node (ref "U1") (pin "39") (pinfunction "PB3/JTDO/TRACESWO_39") (pintype "passive"))
    )
    (net (code "58") (name "unconnected-(U1-PB4{slash}JNTRST-Pad40)") (class "Default")
      (node (ref "U1") (pin "40") (pinfunction "PB4/JNTRST_40") (pintype "passive"))
    )
    (net (code "59") (name "unconnected-(U1-PC13{slash}ANT1-Pad2)") (class "Default")
      (node (ref "U1") (pin "2") (pinfunction "PC13/ANT1_2") (pintype "passive"))
    )
    (net (code "60") (name "unconnected-(U1-PC14{slash}OSC32-Pad3)") (class "Default")
      (node (ref "U1") (pin "3") (pinfunction "PC14/OSC32_3") (pintype "passive"))
    )
    (net (code "61") (name "unconnected-(U1-PC15{slash}OSC32-Pad4)") (class "Default")
      (node (ref "U1") (pin "4") (pinfunction "PC15/OSC32_4") (pintype "passive"))
    )
    (net (code "62") (name "unconnected-(U3-BYP-Pad4)") (class "Default")
      (node (ref "U3") (pin "4") (pinfunction "BYP_4") (pintype "passive+no_connect"))
    )
    (net (code "63") (name "unconnected-(U4-CTS-Pad23)") (class "Default")
      (node (ref "U4") (pin "23") (pinfunction "CTS_23") (pintype "passive+no_connect"))
    )
    (net (code "64") (name "unconnected-(U4-DCD-Pad1)") (class "Default")
      (node (ref "U4") (pin "1") (pinfunction "DCD_1") (pintype "passive+no_connect"))
    )
    (net (code "65") (name "unconnected-(U4-DSR-Pad27)") (class "Default")
      (node (ref "U4") (pin "27") (pinfunction "DSR_27") (pintype "passive+no_connect"))
    )
    (net (code "66") (name "unconnected-(U4-DTR-Pad28)") (class "Default")
      (node (ref "U4") (pin "28") (pinfunction "DTR_28") (pintype "passive+no_connect"))
    )
    (net (code "67") (name "unconnected-(U4-NC-Pad10)") (class "Default")
      (node (ref "U4") (pin "10") (pinfunction "NC_10") (pintype "passive+no_connect"))
    )
    (net (code "68") (name "unconnected-(U4-NC-Pad13)") (class "Default")
      (node (ref "U4") (pin "13") (pinfunction "NC_13") (pintype "passive+no_connect"))
    )
    (net (code "69") (name "unconnected-(U4-NC-Pad14)") (class "Default")
      (node (ref "U4") (pin "14") (pinfunction "NC_14") (pintype "passive+no_connect"))
    )
    (net (code "70") (name "unconnected-(U4-NC-Pad16)") (class "Default")
      (node (ref "U4") (pin "16") (pinfunction "NC_16") (pintype "passive+no_connect"))
    )
    (net (code "71") (name "unconnected-(U4-NC-Pad17)") (class "Default")
      (node (ref "U4") (pin "17") (pinfunction "NC_17") (pintype "passive+no_connect"))
    )
    (net (code "72") (name "unconnected-(U4-NC-Pad18)") (class "Default")
      (node (ref "U4") (pin "18") (pinfunction "NC_18") (pintype "passive+no_connect"))
    )
    (net (code "73") (name "unconnected-(U4-NC-Pad19)") (class "Default")
      (node (ref "U4") (pin "19") (pinfunction "NC_19") (pintype "passive+no_connect"))
    )
    (net (code "74") (name "unconnected-(U4-NC-Pad20)") (class "Default")
      (node (ref "U4") (pin "20") (pinfunction "NC_20") (pintype "passive+no_connect"))
    )
    (net (code "75") (name "unconnected-(U4-NC-Pad21)") (class "Default")
      (node (ref "U4") (pin "21") (pinfunction "NC_21") (pintype "passive+no_connect"))
    )
    (net (code "76") (name "unconnected-(U4-NC-Pad22)") (class "Default")
      (node (ref "U4") (pin "22") (pinfunction "NC_22") (pintype "passive+no_connect"))
    )
    (net (code "77") (name "unconnected-(U4-RI-Pad2)") (class "Default")
      (node (ref "U4") (pin "2") (pinfunction "RI_2") (pintype "passive+no_connect"))
    )
    (net (code "78") (name "unconnected-(U4-RTS-Pad24)") (class "Default")
      (node (ref "U4") (pin "24") (pinfunction "RTS_24") (pintype "passive+no_connect"))
    )
    (net (code "79") (name "unconnected-(U4-SUSPEND-Pad12)") (class "Default")
      (node (ref "U4") (pin "12") (pinfunction "SUSPEND_12") (pintype "passive+no_connect"))
    )
    (net (code "80") (name "unconnected-(U4-SUSPEND{slash}-Pad11)") (class "Default")
      (node (ref "U4") (pin "11") (pinfunction "SUSPEND/_11") (pintype "passive+no_connect"))
    )
  )
)
